# 03_-_CONTROLLER.net
KiCad netlist of a schematic drawn in Altium Designer
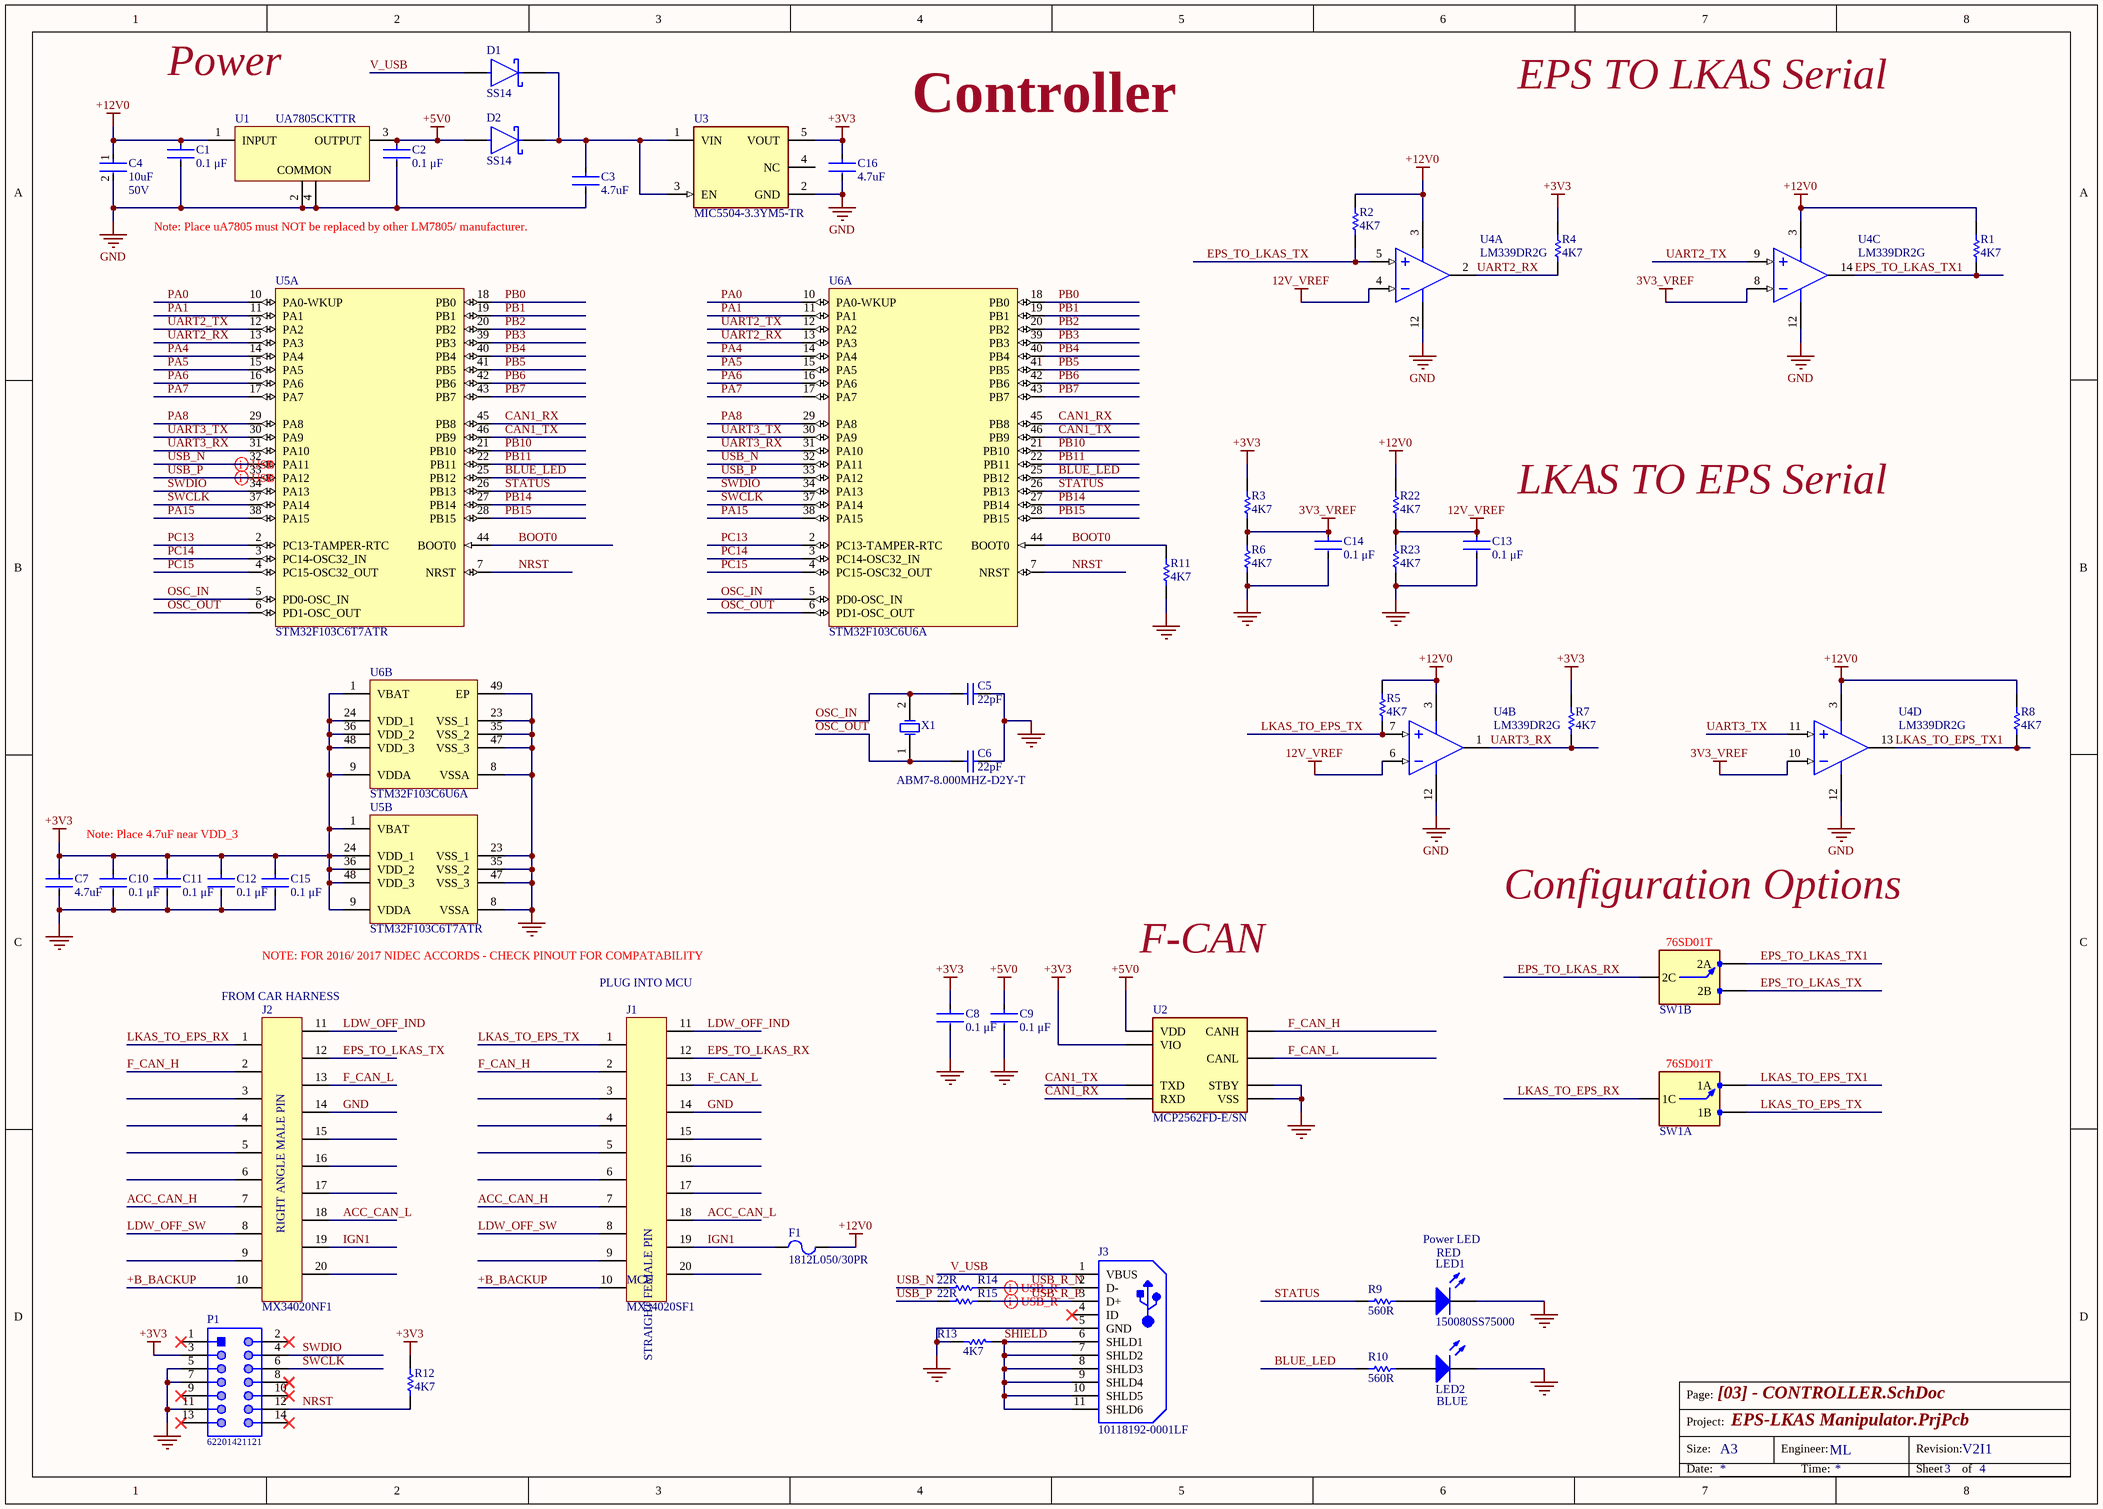
[diagram p0: [03] - CONTROLLER.SchDoc]

(export (version "E")
  (design (tool "Eeschema 10.0.6"))
  (components
    (comp (ref "C1")
      (value "C0603C104M3RACTU")
      (footprint "FP-C0603C-CF-MFG")
      (description "CAP CER 0.1UF 25V X7R 0603")
      (fields
        (field (name "CAPACITANCE") "0.1 μF")
        (field (name "OCTOPART") "https://octopart.com/c0603c104m3ractu-kemet-95914")
        (field (name "MANUFACTURER") "KEMET")
      )
      (libsource (lib "Altium Content Vault") (part "b4654b650e69147ec39a6b967a45e02"))
    )
    (comp (ref "C2")
      (value "C0603C104M3RACTU")
      (footprint "FP-C0603C-CF-MFG")
      (description "CAP CER 0.1UF 25V X7R 0603")
      (fields
        (field (name "CAPACITANCE") "0.1 μF")
        (field (name "OCTOPART") "https://octopart.com/c0603c104m3ractu-kemet-95914")
        (field (name "MANUFACTURER") "KEMET")
      )
      (libsource (lib "Altium Content Vault") (part "b4654b650e69147ec39a6b967a45e02"))
    )
    (comp (ref "C3")
      (value "CL10B475KQ8NQNC")
      (footprint "FP-CL10-IPC_C")
      (description "CAP CER 4.7UF 6.3V X7R 0603")
      (fields
        (field (name "TOLERANCE") "10%")
        (field (name "CAPACITANCE") "4.7uF")
        (field (name "OCTOPART") "https://octopart.com/cl10b475kq8nqnc-samsung-24957976")
      )
      (libsource (lib "Altium Content Vault") (part "11868f565c42a9108669ba33697ecf6"))
    )
    (comp (ref "C4")
      (value "10uF")
      (footprint "FP-CL31-IPC_C")
      (description "CAP CER 10UF 50V X5R 1206")
      (fields
        (field (name "TOLERANCE") "10%")
        (field (name "MANUFACTURER") "Samsung")
        (field (name "VOLTAGE") "50V")
      )
      (libsource (lib "") (part "11868f565c42a9108669ba33697ecf6_1"))
    )
    (comp (ref "C5")
      (value "GRM1885C1H220JA01D")
      (footprint "CAPC1608X90X35ML10T15")
      (description "Chip Capacitor, 22 pF, +/- 5%, 50 V, -55 to 125 degC, 0603 (1608 Metric), RoHS, Tape and Reel")
      (fields (field (name "CAPACITANCE") "22pF") (field (name "MANUFACTURER") "Murata"))
      (libsource (lib "Altium Content Vault") (part "CAP-NP-2"))
    )
    (comp (ref "C6")
      (value "GRM1885C1H220JA01D")
      (footprint "CAPC1608X90X35ML10T15")
      (description "Chip Capacitor, 22 pF, +/- 5%, 50 V, -55 to 125 degC, 0603 (1608 Metric), RoHS, Tape and Reel")
      (fields (field (name "CAPACITANCE") "22pF") (field (name "MANUFACTURER") "Murata"))
      (libsource (lib "Altium Content Vault") (part "CAP-NP-2"))
    )
    (comp (ref "C7")
      (value "CL10B475KQ8NQNC")
      (footprint "FP-CL10-IPC_C")
      (description "CAP CER 4.7UF 6.3V X7R 0603")
      (fields
        (field (name "TOLERANCE") "10%")
        (field (name "CAPACITANCE") "4.7uF")
        (field (name "OCTOPART") "https://octopart.com/cl10b475kq8nqnc-samsung-24957976")
      )
      (libsource (lib "Altium Content Vault") (part "11868f565c42a9108669ba33697ecf6"))
    )
    (comp (ref "C8")
      (value "C0603C104M3RACTU")
      (footprint "FP-C0603C-CF-MFG")
      (description "CAP CER 0.1UF 25V X7R 0603")
      (fields
        (field (name "CAPACITANCE") "0.1 μF")
        (field (name "OCTOPART") "https://octopart.com/c0603c104m3ractu-kemet-95914")
        (field (name "MANUFACTURER") "KEMET")
      )
      (libsource (lib "Altium Content Vault") (part "b4654b650e69147ec39a6b967a45e02"))
    )
    (comp (ref "C9")
      (value "C0603C104M3RACTU")
      (footprint "FP-C0603C-CF-MFG")
      (description "CAP CER 0.1UF 25V X7R 0603")
      (fields
        (field (name "CAPACITANCE") "0.1 μF")
        (field (name "OCTOPART") "https://octopart.com/c0603c104m3ractu-kemet-95914")
        (field (name "MANUFACTURER") "KEMET")
      )
      (libsource (lib "Altium Content Vault") (part "b4654b650e69147ec39a6b967a45e02"))
    )
    (comp (ref "C10")
      (value "C0603C104M3RACTU")
      (footprint "FP-C0603C-CF-MFG")
      (description "CAP CER 0.1UF 25V X7R 0603")
      (fields
        (field (name "CAPACITANCE") "0.1 μF")
        (field (name "OCTOPART") "https://octopart.com/c0603c104m3ractu-kemet-95914")
        (field (name "MANUFACTURER") "KEMET")
      )
      (libsource (lib "Altium Content Vault") (part "b4654b650e69147ec39a6b967a45e02"))
    )
    (comp (ref "C11")
      (value "C0603C104M3RACTU")
      (footprint "FP-C0603C-CF-MFG")
      (description "CAP CER 0.1UF 25V X7R 0603")
      (fields
        (field (name "CAPACITANCE") "0.1 μF")
        (field (name "OCTOPART") "https://octopart.com/c0603c104m3ractu-kemet-95914")
        (field (name "MANUFACTURER") "KEMET")
      )
      (libsource (lib "Altium Content Vault") (part "b4654b650e69147ec39a6b967a45e02"))
    )
    (comp (ref "C12")
      (value "C0603C104M3RACTU")
      (footprint "FP-C0603C-CF-MFG")
      (description "CAP CER 0.1UF 25V X7R 0603")
      (fields
        (field (name "CAPACITANCE") "0.1 μF")
        (field (name "OCTOPART") "https://octopart.com/c0603c104m3ractu-kemet-95914")
        (field (name "MANUFACTURER") "KEMET")
      )
      (libsource (lib "Altium Content Vault") (part "b4654b650e69147ec39a6b967a45e02"))
    )
    (comp (ref "C13")
      (value "C0603C104M3RACTU")
      (footprint "FP-C0603C-CF-MFG")
      (description "CAP CER 0.1UF 25V X7R 0603")
      (fields
        (field (name "CAPACITANCE") "0.1 μF")
        (field (name "OCTOPART") "https://octopart.com/c0603c104m3ractu-kemet-95914")
        (field (name "MANUFACTURER") "KEMET")
      )
      (libsource (lib "Altium Content Vault") (part "b4654b650e69147ec39a6b967a45e02"))
    )
    (comp (ref "C14")
      (value "C0603C104M3RACTU")
      (footprint "FP-C0603C-CF-MFG")
      (description "CAP CER 0.1UF 25V X7R 0603")
      (fields
        (field (name "CAPACITANCE") "0.1 μF")
        (field (name "OCTOPART") "https://octopart.com/c0603c104m3ractu-kemet-95914")
        (field (name "MANUFACTURER") "KEMET")
      )
      (libsource (lib "Altium Content Vault") (part "b4654b650e69147ec39a6b967a45e02"))
    )
    (comp (ref "C15")
      (value "C0603C104M3RACTU")
      (footprint "FP-C0603C-CF-MFG")
      (description "CAP CER 0.1UF 25V X7R 0603")
      (fields
        (field (name "CAPACITANCE") "0.1 μF")
        (field (name "OCTOPART") "https://octopart.com/c0603c104m3ractu-kemet-95914")
        (field (name "MANUFACTURER") "KEMET")
      )
      (libsource (lib "Altium Content Vault") (part "b4654b650e69147ec39a6b967a45e02"))
    )
    (comp (ref "C16")
      (value "CL10B475KQ8NQNC")
      (footprint "FP-CL10-IPC_C")
      (description "CAP CER 4.7UF 6.3V X7R 0603")
      (fields
        (field (name "TOLERANCE") "10%")
        (field (name "CAPACITANCE") "4.7uF")
        (field (name "OCTOPART") "https://octopart.com/cl10b475kq8nqnc-samsung-24957976")
      )
      (libsource (lib "Altium Content Vault") (part "11868f565c42a9108669ba33697ecf6"))
    )
    (comp (ref "D1")
      (value "SS14")
      (footprint "FP-403AE-MFG")
      (description "DIODE SCHOTTKY 40V 1A SMA")
      (fields
        (field (name "MANUFACTURER") "ON Semiconductor")
        (field (name "OCTOPART") "https://octopart.com/ss14-on+semiconductor-29205033")
      )
      (libsource (lib "Altium Content Vault") (part "360ad2f4ac25a952324d13796385471"))
    )
    (comp (ref "D2")
      (value "SS14")
      (footprint "FP-403AE-MFG")
      (description "DIODE SCHOTTKY 40V 1A SMA")
      (fields
        (field (name "MANUFACTURER") "ON Semiconductor")
        (field (name "OCTOPART") "https://octopart.com/ss14-on+semiconductor-29205033")
      )
      (libsource (lib "Altium Content Vault") (part "360ad2f4ac25a952324d13796385471"))
    )
    (comp (ref "F1")
      (value "1812L050/30PR")
      (footprint "LFUS-1812L05030PR_V")
      (description "PTC Resettable Fuse, 0.8 W, 30 V, -40 to 85 degC, 2-Pin SMD, RoHS, Tape and Reel")
      (fields (field (name "MANUFACTURER") "Littelfuse-Inc."))
      (libsource (lib "Altium Content Vault") (part "FUSE-2"))
    )
    (comp (ref "J1")
      (value "MX34020SF1")
      (footprint "MX34020SF1")
      (description "Automotive Connectors Sckt HOUSING 20P")
      (fields (field (name "MANUFACTURER") "JAE Electronics"))
      (libsource (lib "MCU_EPS") (part "MX34020SF1"))
    )
    (comp (ref "J2")
      (value "MX34020NF1")
      (footprint "MX34020NF1")
      (description "JAE MX34 Series, 2.2mm Pitch 20 Way 2 Row Right Angle PCB Header, Solder Termination, 3A")
      (fields (field (name "MANUFACTURER") "JAE Electronics"))
      (libsource (lib "MCU_EPS") (part "MX34020NF1"))
    )
    (comp (ref "J3")
      (value "10118192-0001LF")
      (footprint "FCI-10118192-0001LF-5_V")
      (description "Micro USB B Type Receptacle, -55 to 85 degC, 5-Pin SMD, RoHS, Tape and Reel")
      (fields (field (name "MANUFACTURER") "FCI"))
      (libsource (lib "Altium Content Vault") (part "USB-5-6SHLD"))
    )
    (comp (ref "LED1")
      (value "150080SS75000")
      (footprint "0805_A")
      (description "SMD mono-color Chip LED, WL-SMCW, Super Red")
      (fields (field (name "MANUFACTURER") "Wuerth Elektronik"))
      (libsource (lib "Altium Content Vault") (part "WE-LED_K1A2-2"))
    )
    (comp (ref "LED2")
      (value "150080BS75000")
      (footprint "0805_A")
      (description "SMD mono-color Chip LED, WL-SMCW, Blue")
      (fields (field (name "MANUFACTURER") "Wuerth Elektronik"))
      (libsource (lib "Altium Content Vault") (part "WE-LED_K1A2-2"))
    )
    (comp (ref "P1")
      (value "62201421121")
      (footprint "62201421121")
      (description "THT Vertical Pin Header WR-PHD, Pitch 1.27 mm, Dual Row, 14 pins")
      (fields (field (name "MANUFACTURER") "Wurth Elektronik") (field (name "PUBLISHER") "WurthElektronik"))
      (libsource (lib "Altium Content Vault") (part "WE-CN-2P-M-R14"))
    )
    (comp (ref "R1")
      (value "4K7")
      (footprint "R0603")
      (description "Res Thick Film 0603 4.7K Ohm 1% 1/10W 100ppm/C Molded SMD SMD Paper T/R")
      (fields
        (field (name "MANUFACTURER") "Stackpole Electronics")
        (field (name "MANUFACTURER PART NUMBER") "RMCF0603FT4K70")
      )
      (libsource (lib "LKAS_EPS") (part "RMCF0603FT4K70"))
    )
    (comp (ref "R2")
      (value "4K7")
      (footprint "R0603")
      (description "Res Thick Film 0603 4.7K Ohm 1% 1/10W 100ppm/C Molded SMD SMD Paper T/R")
      (fields
        (field (name "MANUFACTURER") "Stackpole Electronics")
        (field (name "MANUFACTURER PART NUMBER") "RMCF0603FT4K70")
      )
      (libsource (lib "LKAS_EPS") (part "RMCF0603FT4K70"))
    )
    (comp (ref "R3")
      (value "4K7")
      (footprint "R0603")
      (description "Res Thick Film 0603 4.7K Ohm 1% 1/10W 100ppm/C Molded SMD SMD Paper T/R")
      (fields
        (field (name "MANUFACTURER") "Stackpole Electronics")
        (field (name "MANUFACTURER PART NUMBER") "RMCF0603FT4K70")
      )
      (libsource (lib "LKAS_EPS") (part "RMCF0603FT4K70"))
    )
    (comp (ref "R4")
      (value "4K7")
      (footprint "R0603")
      (description "Res Thick Film 0603 4.7K Ohm 1% 1/10W 100ppm/C Molded SMD SMD Paper T/R")
      (fields
        (field (name "MANUFACTURER") "Stackpole Electronics")
        (field (name "MANUFACTURER PART NUMBER") "RMCF0603FT4K70")
      )
      (libsource (lib "LKAS_EPS") (part "RMCF0603FT4K70"))
    )
    (comp (ref "R5")
      (value "4K7")
      (footprint "R0603")
      (description "Res Thick Film 0603 4.7K Ohm 1% 1/10W 100ppm/C Molded SMD SMD Paper T/R")
      (fields
        (field (name "MANUFACTURER") "Stackpole Electronics")
        (field (name "MANUFACTURER PART NUMBER") "RMCF0603FT4K70")
      )
      (libsource (lib "LKAS_EPS") (part "RMCF0603FT4K70"))
    )
    (comp (ref "R6")
      (value "4K7")
      (footprint "R0603")
      (description "Res Thick Film 0603 4.7K Ohm 1% 1/10W 100ppm/C Molded SMD SMD Paper T/R")
      (fields
        (field (name "MANUFACTURER") "Stackpole Electronics")
        (field (name "MANUFACTURER PART NUMBER") "RMCF0603FT4K70")
      )
      (libsource (lib "LKAS_EPS") (part "RMCF0603FT4K70"))
    )
    (comp (ref "R7")
      (value "4K7")
      (footprint "R0603")
      (description "Res Thick Film 0603 4.7K Ohm 1% 1/10W 100ppm/C Molded SMD SMD Paper T/R")
      (fields
        (field (name "MANUFACTURER") "Stackpole Electronics")
        (field (name "MANUFACTURER PART NUMBER") "RMCF0603FT4K70")
      )
      (libsource (lib "LKAS_EPS") (part "RMCF0603FT4K70"))
    )
    (comp (ref "R8")
      (value "4K7")
      (footprint "R0603")
      (description "Res Thick Film 0603 4.7K Ohm 1% 1/10W 100ppm/C Molded SMD SMD Paper T/R")
      (fields
        (field (name "MANUFACTURER") "Stackpole Electronics")
        (field (name "MANUFACTURER PART NUMBER") "RMCF0603FT4K70")
      )
      (libsource (lib "LKAS_EPS") (part "RMCF0603FT4K70"))
    )
    (comp (ref "R9")
      (value "RC0603FR-07560RL")
      (footprint "RESC1608X55X25ML10T15")
      (description "Chip Resistor, 560 Ohm, +/- 1%, 0.1 W, -55 to 155 degC, 0603 (1608 Metric), RoHS, Tape and Reel")
      (fields (field (name "RESISTANCE") "560R") (field (name "TOLERANCE") "1%"))
      (libsource (lib "Altium Content Vault") (part "RES-2"))
    )
    (comp (ref "R10")
      (value "RC0603FR-07560RL")
      (footprint "RESC1608X55X25ML10T15")
      (description "Chip Resistor, 560 Ohm, +/- 1%, 0.1 W, -55 to 155 degC, 0603 (1608 Metric), RoHS, Tape and Reel")
      (fields (field (name "RESISTANCE") "560R") (field (name "TOLERANCE") "1%"))
      (libsource (lib "Altium Content Vault") (part "RES-2"))
    )
    (comp (ref "R11")
      (value "4K7")
      (footprint "R0603")
      (description "Res Thick Film 0603 4.7K Ohm 1% 1/10W 100ppm/C Molded SMD SMD Paper T/R")
      (fields
        (field (name "MANUFACTURER") "Stackpole Electronics")
        (field (name "MANUFACTURER PART NUMBER") "RMCF0603FT4K70")
      )
      (libsource (lib "LKAS_EPS") (part "RMCF0603FT4K70"))
    )
    (comp (ref "R12")
      (value "4K7")
      (footprint "R0603")
      (description "Res Thick Film 0603 4.7K Ohm 1% 1/10W 100ppm/C Molded SMD SMD Paper T/R")
      (fields
        (field (name "MANUFACTURER") "Stackpole Electronics")
        (field (name "MANUFACTURER PART NUMBER") "RMCF0603FT4K70")
      )
      (libsource (lib "LKAS_EPS") (part "RMCF0603FT4K70"))
    )
    (comp (ref "R13")
      (value "4K7")
      (footprint "R0603")
      (description "Res Thick Film 0603 4.7K Ohm 1% 1/10W 100ppm/C Molded SMD SMD Paper T/R")
      (fields
        (field (name "MANUFACTURER") "Stackpole Electronics")
        (field (name "MANUFACTURER PART NUMBER") "RMCF0603FT4K70")
      )
      (libsource (lib "LKAS_EPS") (part "RMCF0603FT4K70"))
    )
    (comp (ref "R14")
      (value "22R")
      (footprint "RESC1609X50X30ML10T20")
      (fields (field (name "MANUFACTURER") "Vishay Dale") (field (name "PART NUMBER") "CRCW060322R0JNTA"))
      (libsource (lib "Altium Content Vault") (part "RES"))
    )
    (comp (ref "R15")
      (value "22R")
      (footprint "RESC1609X50X30ML10T20")
      (fields (field (name "MANUFACTURER") "Vishay Dale") (field (name "PART NUMBER") "CRCW060322R0JNTA"))
      (libsource (lib "Altium Content Vault") (part "RES"))
    )
    (comp (ref "R22")
      (value "4K7")
      (footprint "R0603")
      (description "Res Thick Film 0603 4.7K Ohm 1% 1/10W 100ppm/C Molded SMD SMD Paper T/R")
      (fields
        (field (name "MANUFACTURER") "Stackpole Electronics")
        (field (name "MANUFACTURER PART NUMBER") "RMCF0603FT4K70")
      )
      (libsource (lib "LKAS_EPS") (part "RMCF0603FT4K70"))
    )
    (comp (ref "R23")
      (value "4K7")
      (footprint "R0603")
      (description "Res Thick Film 0603 4.7K Ohm 1% 1/10W 100ppm/C Molded SMD SMD Paper T/R")
      (fields
        (field (name "MANUFACTURER") "Stackpole Electronics")
        (field (name "MANUFACTURER PART NUMBER") "RMCF0603FT4K70")
      )
      (libsource (lib "LKAS_EPS") (part "RMCF0603FT4K70"))
    )
    (comp (ref "SW1")
      (value "76STC02T")
      (footprint "76STC02T")
      (description "SWITCH TOGGLE DIP SPDT 150MA 30V\r\nWIRED:\r\n1  2  3\r\n4  5  6")
      (fields (field (name "MANUFACTURER") "Grayhill"))
      (libsource (lib "LKAS_EPS") (part "76STC02T"))
    )
    (comp (ref "U1")
      (value "UA7805CKTTR")
      (footprint "KTT0003A_V")
      (fields (field (name "TOLERANCE") "1%"))
      (libsource (lib "Altium Content Vault") (part "TI-UA78XX-KTT-3"))
    )
    (comp (ref "U2")
      (value "MCP2562FD-E/SN")
      (footprint "MCP2561")
      (description "8 SOIC 3.90mm(.150in) TUBECAN Flexible Data Rate Transceiver")
      (fields (field (name "MANUFACTURER") "Microchip"))
      (libsource (lib "MCU_EPS") (part "MCP2562FD-E/SN"))
    )
    (comp (ref "U3")
      (value "MIC5504-3.3YM5-TR")
      (footprint "FP-SOT23-5LD-PL-1-MFG")
      (description "IC REG LINEAR 3.3V 300MA SOT23-5")
      (libsource (lib "Altium Content Vault") (part "96048095611b4a9579e1e315950d302"))
    )
    (comp (ref "U4")
      (value "LM339DR2G")
      (footprint "ONSC-SOIC-14-751A-03_V")
      (description "Single Supply Quad Comparators, 0 to 70 degC, 14-Pin SOIC, Pb-Free, Tape and Reel")
      (fields (field (name "MANUFACTURER") "On Semiconductor"))
      (libsource (lib "Altium Content Vault") (part "ONSC-LM239_LM339_LM2901_NCV2901_MC3302_LMV339-14"))
    )
    (comp (ref "U5")
      (value "STM32F103C6T7ATR")
      (footprint "STM-LQFP48_L")
      (libsource (lib "Altium Content Vault") (part "MC-ARM-STM32F103X4_6-SQ48"))
    )
    (comp (ref "U6")
      (value "STM32F103C6U6A")
      (footprint "STM-UFQFPN48_M")
      (libsource (lib "Altium Content Vault") (part "MC-ARM-STM32F103X4_6-SQ49"))
    )
    (comp (ref "X1")
      (value "ABM7-8.000MHZ-D2Y-T")
      (footprint "ABRA-ABM7-2_V")
      (description "Microprocessor Crystal, 8 MHz, 18 PF, -40 to 85 degC, 2-Pin SMD, RoHS, Tape and Reel")
      (fields (field (name "MANUFACTURER") "Abracon"))
      (libsource (lib "Altium Content Vault") (part "XTAL_1-2-2"))
    )
  )
  (nets
    (net (code "1") (name "+3V3") (class "Default")
      (node (ref "C10") (pin "1") (pinfunction "1_1") (pintype "passive"))
      (node (ref "C11") (pin "1") (pinfunction "1_1") (pintype "passive"))
      (node (ref "C12") (pin "1") (pinfunction "1_1") (pintype "passive"))
      (node (ref "C15") (pin "1") (pinfunction "1_1") (pintype "passive"))
      (node (ref "C16") (pin "1") (pinfunction "1_1") (pintype "passive"))
      (node (ref "C7") (pin "1") (pinfunction "1_1") (pintype "passive"))
      (node (ref "C8") (pin "1") (pinfunction "1_1") (pintype "passive"))
      (node (ref "P1") (pin "3") (pinfunction "3_3") (pintype "passive"))
      (node (ref "R12") (pin "2") (pinfunction "2_2") (pintype "passive"))
      (node (ref "R3") (pin "2") (pinfunction "2_2") (pintype "passive"))
      (node (ref "R4") (pin "2") (pinfunction "2_2") (pintype "passive"))
      (node (ref "R7") (pin "2") (pinfunction "2_2") (pintype "passive"))
      (node (ref "U2") (pin "5") (pinfunction "VIO_5") (pintype "passive"))
      (node (ref "U3") (pin "5") (pinfunction "VOUT_5") (pintype "power_in"))
      (node (ref "U5") (pin "1") (pinfunction "VBAT_1") (pintype "power_in"))
      (node (ref "U5") (pin "24") (pinfunction "VDD_1_24") (pintype "power_in"))
      (node (ref "U5") (pin "36") (pinfunction "VDD_2_36") (pintype "power_in"))
      (node (ref "U5") (pin "48") (pinfunction "VDD_3_48") (pintype "power_in"))
      (node (ref "U5") (pin "9") (pinfunction "VDDA_9") (pintype "power_in"))
      (node (ref "U6") (pin "1") (pinfunction "VBAT_1") (pintype "power_in"))
      (node (ref "U6") (pin "24") (pinfunction "VDD_1_24") (pintype "power_in"))
      (node (ref "U6") (pin "36") (pinfunction "VDD_2_36") (pintype "power_in"))
      (node (ref "U6") (pin "48") (pinfunction "VDD_3_48") (pintype "power_in"))
      (node (ref "U6") (pin "9") (pinfunction "VDDA_9") (pintype "power_in"))
    )
    (net (code "2") (name "+5V0") (class "Default")
      (node (ref "C2") (pin "1") (pinfunction "1_1") (pintype "passive"))
      (node (ref "C9") (pin "1") (pinfunction "1_1") (pintype "passive"))
      (node (ref "D2") (pin "1") (pinfunction "A_1") (pintype "passive"))
      (node (ref "U1") (pin "3") (pinfunction "OUTPUT_3") (pintype "power_in"))
      (node (ref "U2") (pin "3") (pinfunction "VDD_3") (pintype "passive"))
    )
    (net (code "3") (name "+12V0") (class "Default")
      (node (ref "C1") (pin "1") (pinfunction "1_1") (pintype "passive"))
      (node (ref "C4") (pin "1") (pinfunction "1_1") (pintype "passive"))
      (node (ref "F1") (pin "2") (pinfunction "2_2") (pintype "passive"))
      (node (ref "R1") (pin "2") (pinfunction "2_2") (pintype "passive"))
      (node (ref "R2") (pin "2") (pinfunction "2_2") (pintype "passive"))
      (node (ref "R22") (pin "2") (pinfunction "2_2") (pintype "passive"))
      (node (ref "R5") (pin "2") (pinfunction "2_2") (pintype "passive"))
      (node (ref "R8") (pin "2") (pinfunction "2_2") (pintype "passive"))
      (node (ref "U1") (pin "1") (pinfunction "INPUT_1") (pintype "power_in"))
      (node (ref "U4") (pin "3") (pinfunction "VCC_3") (pintype "power_in"))
    )
    (net (code "4") (name "/+B_BACKUP") (class "Default")
      (node (ref "J1") (pin "10") (pinfunction "10_10") (pintype "passive"))
      (node (ref "J2") (pin "10") (pinfunction "10_10") (pintype "passive"))
    )
    (net (code "5") (name "/ACC_CAN_H") (class "Default")
      (node (ref "J1") (pin "7") (pinfunction "7_7") (pintype "passive"))
      (node (ref "J2") (pin "7") (pinfunction "7_7") (pintype "passive"))
    )
    (net (code "6") (name "/ACC_CAN_L") (class "Default")
      (node (ref "J1") (pin "18") (pinfunction "18_18") (pintype "passive"))
      (node (ref "J2") (pin "18") (pinfunction "18_18") (pintype "passive"))
    )
    (net (code "7") (name "/BLUE_LED") (class "Default")
      (node (ref "R10") (pin "1") (pinfunction "1_1") (pintype "passive"))
      (node (ref "U5") (pin "25") (pinfunction "PB12_25") (pintype "bidirectional"))
      (node (ref "U6") (pin "25") (pinfunction "PB12_25") (pintype "bidirectional"))
    )
    (net (code "8") (name "/BOOT0") (class "Default")
      (node (ref "R11") (pin "2") (pinfunction "2_2") (pintype "passive"))
      (node (ref "U5") (pin "44") (pinfunction "BOOT0_44") (pintype "input"))
      (node (ref "U6") (pin "44") (pinfunction "BOOT0_44") (pintype "input"))
    )
    (net (code "9") (name "/CAN1_RX") (class "Default")
      (node (ref "U2") (pin "4") (pinfunction "RXD_4") (pintype "passive"))
      (node (ref "U5") (pin "45") (pinfunction "PB8_45") (pintype "bidirectional"))
      (node (ref "U6") (pin "45") (pinfunction "PB8_45") (pintype "bidirectional"))
    )
    (net (code "10") (name "/CAN1_TX") (class "Default")
      (node (ref "U2") (pin "1") (pinfunction "TXD_1") (pintype "passive"))
      (node (ref "U5") (pin "46") (pinfunction "PB9_46") (pintype "bidirectional"))
      (node (ref "U6") (pin "46") (pinfunction "PB9_46") (pintype "bidirectional"))
    )
    (net (code "11") (name "/EPS_TO_LKAS_RX") (class "Default")
      (node (ref "J1") (pin "12") (pinfunction "12_12") (pintype "passive"))
      (node (ref "SW1") (pin "C2") (pinfunction "2C_C2") (pintype "passive"))
    )
    (net (code "12") (name "/EPS_TO_LKAS_TX") (class "Default")
      (node (ref "J2") (pin "12") (pinfunction "12_12") (pintype "passive"))
      (node (ref "R2") (pin "1") (pinfunction "1_1") (pintype "passive"))
      (node (ref "SW1") (pin "2B") (pinfunction "2B_2B") (pintype "passive"))
      (node (ref "U4") (pin "5") (pinfunction "IN1+_5") (pintype "input"))
    )
    (net (code "13") (name "/EPS_TO_LKAS_TX1") (class "Default")
      (node (ref "R1") (pin "1") (pinfunction "1_1") (pintype "passive"))
      (node (ref "SW1") (pin "2A") (pinfunction "2A_2A") (pintype "passive"))
      (node (ref "U4") (pin "14") (pinfunction "OUT3_14") (pintype "open_collector"))
    )
    (net (code "14") (name "/F_CAN_H") (class "Default")
      (node (ref "J1") (pin "2") (pinfunction "2_2") (pintype "passive"))
      (node (ref "J2") (pin "2") (pinfunction "2_2") (pintype "passive"))
      (node (ref "U2") (pin "7") (pinfunction "CANH_7") (pintype "passive"))
    )
    (net (code "15") (name "/F_CAN_L") (class "Default")
      (node (ref "J1") (pin "13") (pinfunction "13_13") (pintype "passive"))
      (node (ref "J2") (pin "13") (pinfunction "13_13") (pintype "passive"))
      (node (ref "U2") (pin "6") (pinfunction "CANL_6") (pintype "passive"))
    )
    (net (code "16") (name "/IGN1") (class "Default")
      (node (ref "F1") (pin "1") (pinfunction "1_1") (pintype "passive"))
      (node (ref "J1") (pin "19") (pinfunction "19_19") (pintype "passive"))
      (node (ref "J2") (pin "19") (pinfunction "19_19") (pintype "passive"))
    )
    (net (code "17") (name "/LDW_OFF_IND") (class "Default")
      (node (ref "J1") (pin "11") (pinfunction "11_11") (pintype "passive"))
      (node (ref "J2") (pin "11") (pinfunction "11_11") (pintype "passive"))
    )
    (net (code "18") (name "/LDW_OFF_SW") (class "Default")
      (node (ref "J1") (pin "8") (pinfunction "8_8") (pintype "passive"))
      (node (ref "J2") (pin "8") (pinfunction "8_8") (pintype "passive"))
    )
    (net (code "19") (name "/LKAS_TO_EPS_RX") (class "Default")
      (node (ref "J2") (pin "1") (pinfunction "1_1") (pintype "passive"))
      (node (ref "SW1") (pin "C1") (pinfunction "1C_C1") (pintype "passive"))
    )
    (net (code "20") (name "/LKAS_TO_EPS_TX") (class "Default")
      (node (ref "J1") (pin "1") (pinfunction "1_1") (pintype "passive"))
      (node (ref "R5") (pin "1") (pinfunction "1_1") (pintype "passive"))
      (node (ref "SW1") (pin "1B") (pinfunction "1B_1B") (pintype "passive"))
      (node (ref "U4") (pin "7") (pinfunction "IN2+_7") (pintype "input"))
    )
    (net (code "21") (name "/LKAS_TO_EPS_TX1") (class "Default")
      (node (ref "R8") (pin "1") (pinfunction "1_1") (pintype "passive"))
      (node (ref "SW1") (pin "1A") (pinfunction "1A_1A") (pintype "passive"))
      (node (ref "U4") (pin "13") (pinfunction "OUT4_13") (pintype "open_collector"))
    )
    (net (code "22") (name "/NRST") (class "Default")
      (node (ref "P1") (pin "12") (pinfunction "12_12") (pintype "passive"))
      (node (ref "R12") (pin "1") (pinfunction "1_1") (pintype "passive"))
      (node (ref "U5") (pin "7") (pinfunction "NRST_7") (pintype "bidirectional"))
      (node (ref "U6") (pin "7") (pinfunction "NRST_7") (pintype "bidirectional"))
    )
    (net (code "23") (name "/OSC_IN") (class "Default")
      (node (ref "C5") (pin "1") (pinfunction "1_1") (pintype "passive"))
      (node (ref "U5") (pin "5") (pinfunction "PD0-OSC_IN_5") (pintype "bidirectional"))
      (node (ref "U6") (pin "5") (pinfunction "PD0-OSC_IN_5") (pintype "bidirectional"))
      (node (ref "X1") (pin "2") (pinfunction "X2_2") (pintype "passive"))
    )
    (net (code "24") (name "/OSC_OUT") (class "Default")
      (node (ref "C6") (pin "1") (pinfunction "1_1") (pintype "passive"))
      (node (ref "U5") (pin "6") (pinfunction "PD1-OSC_OUT_6") (pintype "bidirectional"))
      (node (ref "U6") (pin "6") (pinfunction "PD1-OSC_OUT_6") (pintype "bidirectional"))
      (node (ref "X1") (pin "1") (pinfunction "X1_1") (pintype "passive"))
    )
    (net (code "25") (name "/PA0") (class "Default")
      (node (ref "U5") (pin "10") (pinfunction "PA0-WKUP_10") (pintype "bidirectional"))
      (node (ref "U6") (pin "10") (pinfunction "PA0-WKUP_10") (pintype "bidirectional"))
    )
    (net (code "26") (name "/PA1") (class "Default")
      (node (ref "U5") (pin "11") (pinfunction "PA1_11") (pintype "bidirectional"))
      (node (ref "U6") (pin "11") (pinfunction "PA1_11") (pintype "bidirectional"))
    )
    (net (code "27") (name "/PA4") (class "Default")
      (node (ref "U5") (pin "14") (pinfunction "PA4_14") (pintype "bidirectional"))
      (node (ref "U6") (pin "14") (pinfunction "PA4_14") (pintype "bidirectional"))
    )
    (net (code "28") (name "/PA5") (class "Default")
      (node (ref "U5") (pin "15") (pinfunction "PA5_15") (pintype "bidirectional"))
      (node (ref "U6") (pin "15") (pinfunction "PA5_15") (pintype "bidirectional"))
    )
    (net (code "29") (name "/PA6") (class "Default")
      (node (ref "U5") (pin "16") (pinfunction "PA6_16") (pintype "bidirectional"))
      (node (ref "U6") (pin "16") (pinfunction "PA6_16") (pintype "bidirectional"))
    )
    (net (code "30") (name "/PA7") (class "Default")
      (node (ref "U5") (pin "17") (pinfunction "PA7_17") (pintype "bidirectional"))
      (node (ref "U6") (pin "17") (pinfunction "PA7_17") (pintype "bidirectional"))
    )
    (net (code "31") (name "/PA8") (class "Default")
      (node (ref "U5") (pin "29") (pinfunction "PA8_29") (pintype "bidirectional"))
      (node (ref "U6") (pin "29") (pinfunction "PA8_29") (pintype "bidirectional"))
    )
    (net (code "32") (name "/PA15") (class "Default")
      (node (ref "U5") (pin "38") (pinfunction "PA15_38") (pintype "bidirectional"))
      (node (ref "U6") (pin "38") (pinfunction "PA15_38") (pintype "bidirectional"))
    )
    (net (code "33") (name "/PB0") (class "Default")
      (node (ref "U5") (pin "18") (pinfunction "PB0_18") (pintype "bidirectional"))
      (node (ref "U6") (pin "18") (pinfunction "PB0_18") (pintype "bidirectional"))
    )
    (net (code "34") (name "/PB1") (class "Default")
      (node (ref "U5") (pin "19") (pinfunction "PB1_19") (pintype "bidirectional"))
      (node (ref "U6") (pin "19") (pinfunction "PB1_19") (pintype "bidirectional"))
    )
    (net (code "35") (name "/PB2") (class "Default")
      (node (ref "U5") (pin "20") (pinfunction "PB2_20") (pintype "bidirectional"))
      (node (ref "U6") (pin "20") (pinfunction "PB2_20") (pintype "bidirectional"))
    )
    (net (code "36") (name "/PB3") (class "Default")
      (node (ref "U5") (pin "39") (pinfunction "PB3_39") (pintype "bidirectional"))
      (node (ref "U6") (pin "39") (pinfunction "PB3_39") (pintype "bidirectional"))
    )
    (net (code "37") (name "/PB4") (class "Default")
      (node (ref "U5") (pin "40") (pinfunction "PB4_40") (pintype "bidirectional"))
      (node (ref "U6") (pin "40") (pinfunction "PB4_40") (pintype "bidirectional"))
    )
    (net (code "38") (name "/PB5") (class "Default")
      (node (ref "U5") (pin "41") (pinfunction "PB5_41") (pintype "bidirectional"))
      (node (ref "U6") (pin "41") (pinfunction "PB5_41") (pintype "bidirectional"))
    )
    (net (code "39") (name "/PB6") (class "Default")
      (node (ref "U5") (pin "42") (pinfunction "PB6_42") (pintype "bidirectional"))
      (node (ref "U6") (pin "42") (pinfunction "PB6_42") (pintype "bidirectional"))
    )
    (net (code "40") (name "/PB7") (class "Default")
      (node (ref "U5") (pin "43") (pinfunction "PB7_43") (pintype "bidirectional"))
      (node (ref "U6") (pin "43") (pinfunction "PB7_43") (pintype "bidirectional"))
    )
    (net (code "41") (name "/PB10") (class "Default")
      (node (ref "U5") (pin "21") (pinfunction "PB10_21") (pintype "bidirectional"))
      (node (ref "U6") (pin "21") (pinfunction "PB10_21") (pintype "bidirectional"))
    )
    (net (code "42") (name "/PB11") (class "Default")
      (node (ref "U5") (pin "22") (pinfunction "PB11_22") (pintype "bidirectional"))
      (node (ref "U6") (pin "22") (pinfunction "PB11_22") (pintype "bidirectional"))
    )
    (net (code "43") (name "/PB14") (class "Default")
      (node (ref "U5") (pin "27") (pinfunction "PB14_27") (pintype "bidirectional"))
      (node (ref "U6") (pin "27") (pinfunction "PB14_27") (pintype "bidirectional"))
    )
    (net (code "44") (name "/PB15") (class "Default")
      (node (ref "U5") (pin "28") (pinfunction "PB15_28") (pintype "bidirectional"))
      (node (ref "U6") (pin "28") (pinfunction "PB15_28") (pintype "bidirectional"))
    )
    (net (code "45") (name "/PC13") (class "Default")
      (node (ref "U5") (pin "2") (pinfunction "PC13-TAMPER-RTC_2") (pintype "bidirectional"))
      (node (ref "U6") (pin "2") (pinfunction "PC13-TAMPER-RTC_2") (pintype "bidirectional"))
    )
    (net (code "46") (name "/PC14") (class "Default")
      (node (ref "U5") (pin "3") (pinfunction "PC14-OSC32_IN_3") (pintype "bidirectional"))
      (node (ref "U6") (pin "3") (pinfunction "PC14-OSC32_IN_3") (pintype "bidirectional"))
    )
    (net (code "47") (name "/PC15") (class "Default")
      (node (ref "U5") (pin "4") (pinfunction "PC15-OSC32_OUT_4") (pintype "bidirectional"))
      (node (ref "U6") (pin "4") (pinfunction "PC15-OSC32_OUT_4") (pintype "bidirectional"))
    )
    (net (code "48") (name "/SHIELD") (class "Default")
      (node (ref "J3") (pin "10") (pinfunction "SHLD5_10") (pintype "passive"))
      (node (ref "J3") (pin "11") (pinfunction "SHLD6_11") (pintype "passive"))
      (node (ref "J3") (pin "6") (pinfunction "SHLD1_6") (pintype "passive"))
      (node (ref "J3") (pin "7") (pinfunction "SHLD2_7") (pintype "passive"))
      (node (ref "J3") (pin "8") (pinfunction "SHLD3_8") (pintype "passive"))
      (node (ref "J3") (pin "9") (pinfunction "SHLD4_9") (pintype "passive"))
      (node (ref "R13") (pin "1") (pinfunction "1_1") (pintype "passive"))
    )
    (net (code "49") (name "/STATUS") (class "Default")
      (node (ref "R9") (pin "1") (pinfunction "1_1") (pintype "passive"))
      (node (ref "U5") (pin "26") (pinfunction "PB13_26") (pintype "bidirectional"))
      (node (ref "U6") (pin "26") (pinfunction "PB13_26") (pintype "bidirectional"))
    )
    (net (code "50") (name "/SWCLK") (class "Default")
      (node (ref "P1") (pin "6") (pinfunction "6_6") (pintype "passive"))
      (node (ref "U5") (pin "37") (pinfunction "PA14_37") (pintype "bidirectional"))
      (node (ref "U6") (pin "37") (pinfunction "PA14_37") (pintype "bidirectional"))
    )
    (net (code "51") (name "/SWDIO") (class "Default")
      (node (ref "P1") (pin "4") (pinfunction "4_4") (pintype "passive"))
      (node (ref "U5") (pin "34") (pinfunction "PA13_34") (pintype "bidirectional"))
      (node (ref "U6") (pin "34") (pinfunction "PA13_34") (pintype "bidirectional"))
    )
    (net (code "52") (name "/UART2_RX") (class "Default")
      (node (ref "R4") (pin "1") (pinfunction "1_1") (pintype "passive"))
      (node (ref "U4") (pin "2") (pinfunction "OUT1_2") (pintype "open_collector"))
      (node (ref "U5") (pin "13") (pinfunction "PA3_13") (pintype "bidirectional"))
      (node (ref "U6") (pin "13") (pinfunction "PA3_13") (pintype "bidirectional"))
    )
    (net (code "53") (name "/UART2_TX") (class "Default")
      (node (ref "U4") (pin "9") (pinfunction "IN3+_9") (pintype "input"))
      (node (ref "U5") (pin "12") (pinfunction "PA2_12") (pintype "bidirectional"))
      (node (ref "U6") (pin "12") (pinfunction "PA2_12") (pintype "bidirectional"))
    )
    (net (code "54") (name "/UART3_RX") (class "Default")
      (node (ref "R7") (pin "1") (pinfunction "1_1") (pintype "passive"))
      (node (ref "U4") (pin "1") (pinfunction "OUT2_1") (pintype "open_collector"))
      (node (ref "U5") (pin "31") (pinfunction "PA10_31") (pintype "bidirectional"))
      (node (ref "U6") (pin "31") (pinfunction "PA10_31") (pintype "bidirectional"))
    )
    (net (code "55") (name "/UART3_TX") (class "Default")
      (node (ref "U4") (pin "11") (pinfunction "IN4+_11") (pintype "input"))
      (node (ref "U5") (pin "30") (pinfunction "PA9_30") (pintype "bidirectional"))
      (node (ref "U6") (pin "30") (pinfunction "PA9_30") (pintype "bidirectional"))
    )
    (net (code "56") (name "/USB_N") (class "Default")
      (node (ref "R14") (pin "1") (pinfunction "1_1") (pintype "passive"))
      (node (ref "U5") (pin "32") (pinfunction "PA11_32") (pintype "bidirectional"))
      (node (ref "U6") (pin "32") (pinfunction "PA11_32") (pintype "bidirectional"))
    )
    (net (code "57") (name "/USB_P") (class "Default")
      (node (ref "R15") (pin "1") (pinfunction "1_1") (pintype "passive"))
      (node (ref "U5") (pin "33") (pinfunction "PA12_33") (pintype "bidirectional"))
      (node (ref "U6") (pin "33") (pinfunction "PA12_33") (pintype "bidirectional"))
    )
    (net (code "58") (name "/USB_R_N") (class "Default")
      (node (ref "J3") (pin "2") (pinfunction "D-_2") (pintype "passive"))
      (node (ref "R14") (pin "2") (pinfunction "2_2") (pintype "passive"))
    )
    (net (code "59") (name "/USB_R_P") (class "Default")
      (node (ref "J3") (pin "3") (pinfunction "D+_3") (pintype "passive"))
      (node (ref "R15") (pin "2") (pinfunction "2_2") (pintype "passive"))
    )
    (net (code "60") (name "/V_USB") (class "Default")
      (node (ref "D1") (pin "1") (pinfunction "A_1") (pintype "passive"))
      (node (ref "J3") (pin "1") (pinfunction "VBUS_1") (pintype "passive"))
    )
    (net (code "61") (name "3V3_VREF") (class "Default")
      (node (ref "C14") (pin "1") (pinfunction "1_1") (pintype "passive"))
      (node (ref "R3") (pin "1") (pinfunction "1_1") (pintype "passive"))
      (node (ref "R6") (pin "2") (pinfunction "2_2") (pintype "passive"))
      (node (ref "U4") (pin "10") (pinfunction "IN4-_10") (pintype "input"))
      (node (ref "U4") (pin "8") (pinfunction "IN3-_8") (pintype "input"))
    )
    (net (code "62") (name "12V_VREF") (class "Default")
      (node (ref "C13") (pin "1") (pinfunction "1_1") (pintype "passive"))
      (node (ref "R22") (pin "1") (pinfunction "1_1") (pintype "passive"))
      (node (ref "R23") (pin "2") (pinfunction "2_2") (pintype "passive"))
      (node (ref "U4") (pin "4") (pinfunction "IN1-_4") (pintype "input"))
      (node (ref "U4") (pin "6") (pinfunction "IN2-_6") (pintype "input"))
    )
    (net (code "63") (name "GND") (class "Default")
      (node (ref "C1") (pin "2") (pinfunction "2_2") (pintype "passive"))
      (node (ref "C10") (pin "2") (pinfunction "2_2") (pintype "passive"))
      (node (ref "C11") (pin "2") (pinfunction "2_2") (pintype "passive"))
      (node (ref "C12") (pin "2") (pinfunction "2_2") (pintype "passive"))
      (node (ref "C13") (pin "2") (pinfunction "2_2") (pintype "passive"))
      (node (ref "C14") (pin "2") (pinfunction "2_2") (pintype "passive"))
      (node (ref "C15") (pin "2") (pinfunction "2_2") (pintype "passive"))
      (node (ref "C16") (pin "2") (pinfunction "2_2") (pintype "passive"))
      (node (ref "C2") (pin "2") (pinfunction "2_2") (pintype "passive"))
      (node (ref "C3") (pin "2") (pinfunction "2_2") (pintype "passive"))
      (node (ref "C4") (pin "2") (pinfunction "2_2") (pintype "passive"))
      (node (ref "C5") (pin "2") (pinfunction "2_2") (pintype "passive"))
      (node (ref "C6") (pin "2") (pinfunction "2_2") (pintype "passive"))
      (node (ref "C7") (pin "2") (pinfunction "2_2") (pintype "passive"))
      (node (ref "C8") (pin "2") (pinfunction "2_2") (pintype "passive"))
      (node (ref "C9") (pin "2") (pinfunction "2_2") (pintype "passive"))
      (node (ref "J1") (pin "14") (pinfunction "14_14") (pintype "passive"))
      (node (ref "J2") (pin "14") (pinfunction "14_14") (pintype "passive"))
      (node (ref "J3") (pin "5") (pinfunction "GND_5") (pintype "passive"))
      (node (ref "LED1") (pin "1") (pinfunction "K_1") (pintype "passive"))
      (node (ref "LED2") (pin "1") (pinfunction "K_1") (pintype "passive"))
      (node (ref "P1") (pin "11") (pinfunction "11_11") (pintype "passive"))
      (node (ref "P1") (pin "5") (pinfunction "5_5") (pintype "passive"))
      (node (ref "P1") (pin "7") (pinfunction "7_7") (pintype "passive"))
      (node (ref "R11") (pin "1") (pinfunction "1_1") (pintype "passive"))
      (node (ref "R13") (pin "2") (pinfunction "2_2") (pintype "passive"))
      (node (ref "R23") (pin "1") (pinfunction "1_1") (pintype "passive"))
      (node (ref "R6") (pin "1") (pinfunction "1_1") (pintype "passive"))
      (node (ref "U1") (pin "2") (pinfunction "COMMON_2") (pintype "power_in"))
      (node (ref "U1") (pin "4") (pinfunction "COMMON_4") (pintype "power_in"))
      (node (ref "U2") (pin "2") (pinfunction "VSS_2") (pintype "passive"))
      (node (ref "U2") (pin "8") (pinfunction "STBY_8") (pintype "passive"))
      (node (ref "U3") (pin "2") (pinfunction "GND_2") (pintype "power_in"))
      (node (ref "U4") (pin "12") (pinfunction "GND_12") (pintype "power_in"))
      (node (ref "U5") (pin "23") (pinfunction "VSS_1_23") (pintype "power_in"))
      (node (ref "U5") (pin "35") (pinfunction "VSS_2_35") (pintype "power_in"))
      (node (ref "U5") (pin "47") (pinfunction "VSS_3_47") (pintype "power_in"))
      (node (ref "U5") (pin "8") (pinfunction "VSSA_8") (pintype "power_in"))
      (node (ref "U6") (pin "23") (pinfunction "VSS_1_23") (pintype "power_in"))
      (node (ref "U6") (pin "35") (pinfunction "VSS_2_35") (pintype "power_in"))
      (node (ref "U6") (pin "47") (pinfunction "VSS_3_47") (pintype "power_in"))
      (node (ref "U6") (pin "49") (pinfunction "EP_49") (pintype "power_in"))
      (node (ref "U6") (pin "8") (pinfunction "VSSA_8") (pintype "power_in"))
    )
    (net (code "64") (name "Net-(D1-C)") (class "Default")
      (node (ref "C3") (pin "1") (pinfunction "1_1") (pintype "passive"))
      (node (ref "D1") (pin "2") (pinfunction "C_2") (pintype "passive"))
      (node (ref "D2") (pin "2") (pinfunction "C_2") (pintype "passive"))
      (node (ref "U3") (pin "1") (pinfunction "VIN_1") (pintype "power_in"))
      (node (ref "U3") (pin "3") (pinfunction "EN_3") (pintype "input"))
    )
    (net (code "65") (name "Net-(LED1-A)") (class "Default")
      (node (ref "LED1") (pin "2") (pinfunction "A_2") (pintype "passive"))
      (node (ref "R9") (pin "2") (pinfunction "2_2") (pintype "passive"))
    )
    (net (code "66") (name "Net-(LED2-A)") (class "Default")
      (node (ref "LED2") (pin "2") (pinfunction "A_2") (pintype "passive"))
      (node (ref "R10") (pin "2") (pinfunction "2_2") (pintype "passive"))
    )
    (net (code "67") (name "unconnected-(J1-Pad3)") (class "Default")
      (node (ref "J1") (pin "3") (pinfunction "3_3") (pintype "passive"))
    )
    (net (code "68") (name "unconnected-(J1-Pad4)") (class "Default")
      (node (ref "J1") (pin "4") (pinfunction "4_4") (pintype "passive"))
    )
    (net (code "69") (name "unconnected-(J1-Pad5)") (class "Default")
      (node (ref "J1") (pin "5") (pinfunction "5_5") (pintype "passive"))
    )
    (net (code "70") (name "unconnected-(J1-Pad6)") (class "Default")
      (node (ref "J1") (pin "6") (pinfunction "6_6") (pintype "passive"))
    )
    (net (code "71") (name "unconnected-(J1-Pad9)") (class "Default")
      (node (ref "J1") (pin "9") (pinfunction "9_9") (pintype "passive"))
    )
    (net (code "72") (name "unconnected-(J1-Pad15)") (class "Default")
      (node (ref "J1") (pin "15") (pinfunction "15_15") (pintype "passive"))
    )
    (net (code "73") (name "unconnected-(J1-Pad16)") (class "Default")
      (node (ref "J1") (pin "16") (pinfunction "16_16") (pintype "passive"))
    )
    (net (code "74") (name "unconnected-(J1-Pad17)") (class "Default")
      (node (ref "J1") (pin "17") (pinfunction "17_17") (pintype "passive"))
    )
    (net (code "75") (name "unconnected-(J1-Pad20)") (class "Default")
      (node (ref "J1") (pin "20") (pinfunction "20_20") (pintype "passive"))
    )
    (net (code "76") (name "unconnected-(J2-Pad3)") (class "Default")
      (node (ref "J2") (pin "3") (pinfunction "3_3") (pintype "passive"))
    )
    (net (code "77") (name "unconnected-(J2-Pad4)") (class "Default")
      (node (ref "J2") (pin "4") (pinfunction "4_4") (pintype "passive"))
    )
    (net (code "78") (name "unconnected-(J2-Pad5)") (class "Default")
      (node (ref "J2") (pin "5") (pinfunction "5_5") (pintype "passive"))
    )
    (net (code "79") (name "unconnected-(J2-Pad6)") (class "Default")
      (node (ref "J2") (pin "6") (pinfunction "6_6") (pintype "passive"))
    )
    (net (code "80") (name "unconnected-(J2-Pad9)") (class "Default")
      (node (ref "J2") (pin "9") (pinfunction "9_9") (pintype "passive"))
    )
    (net (code "81") (name "unconnected-(J2-Pad15)") (class "Default")
      (node (ref "J2") (pin "15") (pinfunction "15_15") (pintype "passive"))
    )
    (net (code "82") (name "unconnected-(J2-Pad16)") (class "Default")
      (node (ref "J2") (pin "16") (pinfunction "16_16") (pintype "passive"))
    )
    (net (code "83") (name "unconnected-(J2-Pad17)") (class "Default")
      (node (ref "J2") (pin "17") (pinfunction "17_17") (pintype "passive"))
    )
    (net (code "84") (name "unconnected-(J2-Pad20)") (class "Default")
      (node (ref "J2") (pin "20") (pinfunction "20_20") (pintype "passive"))
    )
    (net (code "85") (name "unconnected-(J3-ID-Pad4)") (class "Default")
      (node (ref "J3") (pin "4") (pinfunction "ID_4") (pintype "passive+no_connect"))
    )
    (net (code "86") (name "unconnected-(P1-Pad1)") (class "Default")
      (node (ref "P1") (pin "1") (pinfunction "1_1") (pintype "passive+no_connect"))
    )
    (net (code "87") (name "unconnected-(P1-Pad2)") (class "Default")
      (node (ref "P1") (pin "2") (pinfunction "2_2") (pintype "passive+no_connect"))
    )
    (net (code "88") (name "unconnected-(P1-Pad8)") (class "Default")
      (node (ref "P1") (pin "8") (pinfunction "8_8") (pintype "passive+no_connect"))
    )
    (net (code "89") (name "unconnected-(P1-Pad9)") (class "Default")
      (node (ref "P1") (pin "9") (pinfunction "9_9") (pintype "passive+no_connect"))
    )
    (net (code "90") (name "unconnected-(P1-Pad10)") (class "Default")
      (node (ref "P1") (pin "10") (pinfunction "10_10") (pintype "passive+no_connect"))
    )
    (net (code "91") (name "unconnected-(P1-Pad13)") (class "Default")
      (node (ref "P1") (pin "13") (pinfunction "13_13") (pintype "passive+no_connect"))
    )
    (net (code "92") (name "unconnected-(P1-Pad14)") (class "Default")
      (node (ref "P1") (pin "14") (pinfunction "14_14") (pintype "passive+no_connect"))
    )
    (net (code "93") (name "unconnected-(U3-NC-Pad4)") (class "Default")
      (node (ref "U3") (pin "4") (pinfunction "NC_4") (pintype "passive"))
    )
  )
)
